# ACS_schematic.net
KiCad netlist of a schematic drawn in EAGLE
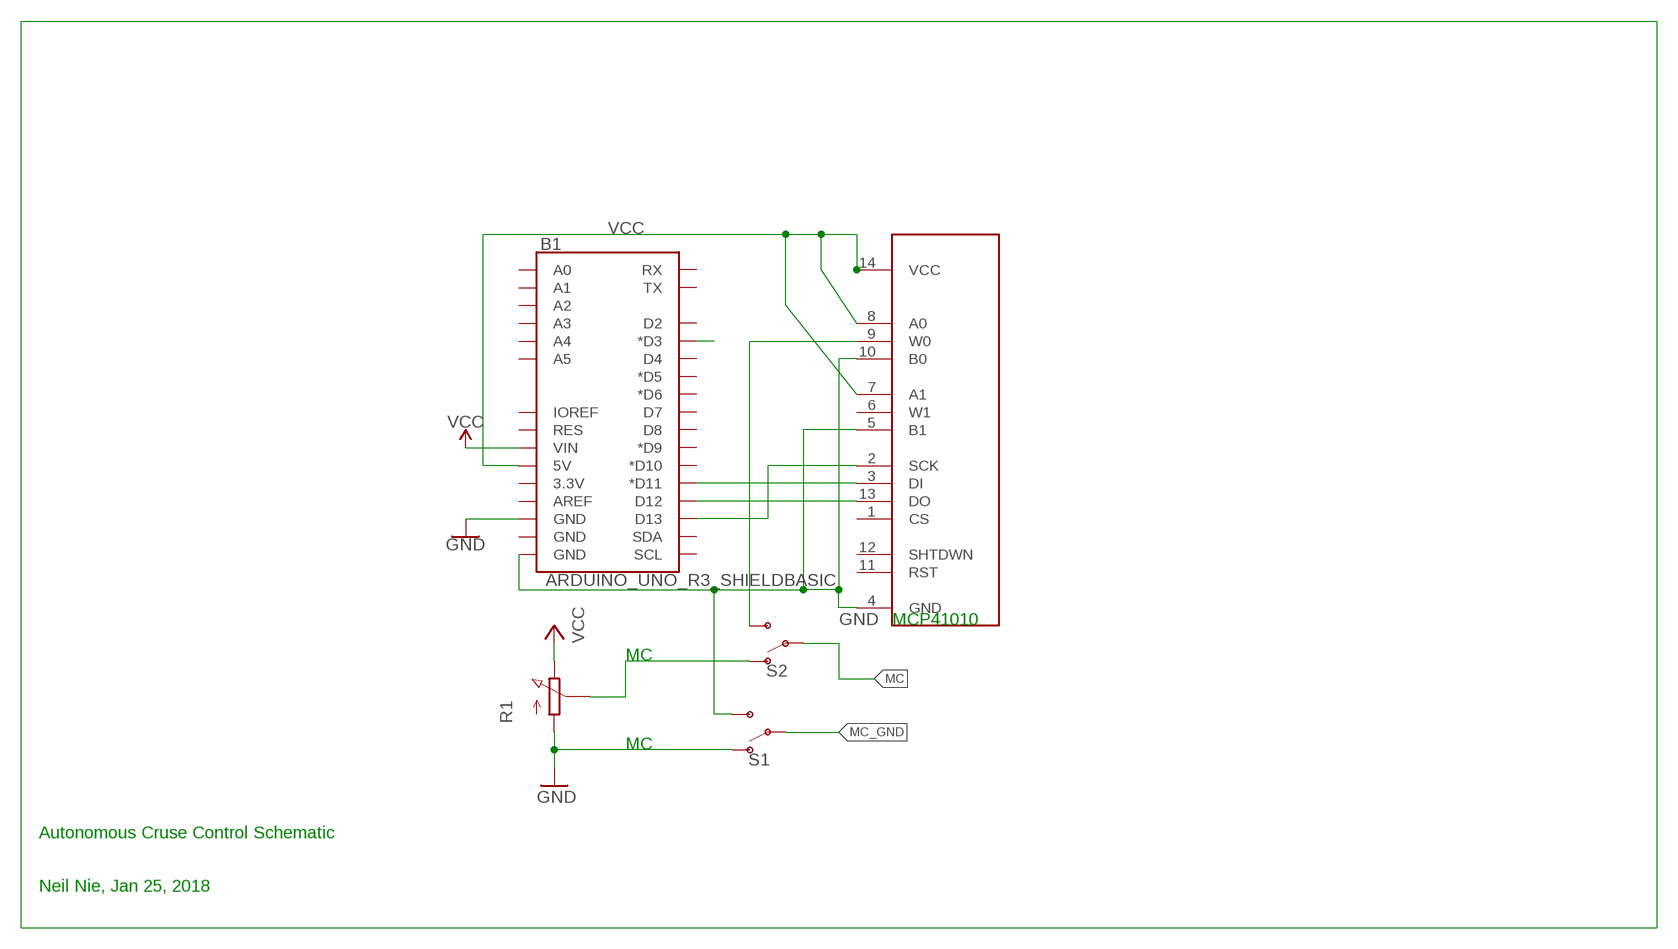
[diagram p0: schematic, sheet 1]

(export (version "E")
  (design (tool "Eeschema 10.0.6"))
  (components
    (comp (ref "B1")
      (value "ARDUINO_UNO_R3_SHIELDBASIC")
      (footprint "eagle-import:UNO_R3_SHIELD")
      (libsource (lib "eagle-import") (part "ARDUINO_UNO_R3_SHIELDBASIC"))
    )
    (comp (ref "MCP41010")
      (value "MCP42XXX")
      (footprint "eagle-import:SO014")
      (libsource (lib "eagle-import") (part "MCP42XXX"))
    )
    (comp (ref "R1")
      (value "PC25")
      (footprint "eagle-import:PC25")
      (fields (field (name "MF") "CLAROSTAT") (field (name "MPN") "308NPC25KS"))
      (libsource (lib "eagle-import") (part "PC25"))
    )
    (comp (ref "S1")
      (value "SWITCH-SPDT-PTH-11.6X4.0MM")
      (footprint "eagle-import:SWITCH_SPDT_PTH_11.6X4.0MM")
      (libsource (lib "eagle-import") (part "SWITCH-SPDT-PTH-11.6X4.0MM"))
    )
    (comp (ref "S2")
      (value "SWITCH-SPDT-PTH-11.6X4.0MM")
      (footprint "eagle-import:SWITCH_SPDT_PTH_11.6X4.0MM")
      (libsource (lib "eagle-import") (part "SWITCH-SPDT-PTH-11.6X4.0MM"))
    )
  )
  (nets
    (net (code "1") (name "GND") (class "Default")
      (node (ref "B1") (pin "GND@0") (pinfunction "GND_GND@0") (pintype "bidirectional"))
      (node (ref "B1") (pin "GND@2") (pinfunction "GND_GND@2") (pintype "bidirectional"))
      (node (ref "MCP41010") (pin "10") (pinfunction "B0_10") (pintype "bidirectional"))
      (node (ref "MCP41010") (pin "4") (pinfunction "GND_4") (pintype "bidirectional"))
      (node (ref "MCP41010") (pin "5") (pinfunction "B1_5") (pintype "bidirectional"))
      (node (ref "R1") (pin "A") (pinfunction "A_A") (pintype "passive"))
      (node (ref "S1") (pin "1") (pinfunction "O_1") (pintype "passive"))
      (node (ref "S1") (pin "3") (pinfunction "S_3") (pintype "passive"))
    )
    (net (code "2") (name "MC") (class "Default")
      (node (ref "S2") (pin "2") (pinfunction "P_2") (pintype "passive"))
    )
    (net (code "3") (name "MC_GND") (class "Default")
      (node (ref "S1") (pin "2") (pinfunction "P_2") (pintype "passive"))
    )
    (net (code "4") (name "Net-(B1-*D11)") (class "Default")
      (node (ref "B1") (pin "D11") (pinfunction "*D11_D11") (pintype "bidirectional"))
      (node (ref "MCP41010") (pin "3") (pinfunction "DI_3") (pintype "bidirectional"))
    )
    (net (code "5") (name "Net-(MCP41010-DO)") (class "Default")
      (node (ref "B1") (pin "D12") (pinfunction "D12_D12") (pintype "bidirectional"))
      (node (ref "MCP41010") (pin "13") (pinfunction "DO_13") (pintype "bidirectional"))
    )
    (net (code "6") (name "Net-(MCP41010-SCK)") (class "Default")
      (node (ref "B1") (pin "D13") (pinfunction "D13_D13") (pintype "bidirectional"))
      (node (ref "MCP41010") (pin "2") (pinfunction "SCK_2") (pintype "bidirectional"))
    )
    (net (code "7") (name "Net-(MCP41010-W0)") (class "Default")
      (node (ref "MCP41010") (pin "9") (pinfunction "W0_9") (pintype "bidirectional"))
      (node (ref "S2") (pin "3") (pinfunction "S_3") (pintype "passive"))
    )
    (net (code "8") (name "Net-(S2-O)") (class "Default")
      (node (ref "R1") (pin "S") (pinfunction "S_S") (pintype "passive"))
      (node (ref "S2") (pin "1") (pinfunction "O_1") (pintype "passive"))
    )
    (net (code "9") (name "VCC") (class "Default")
      (node (ref "B1") (pin "5V") (pinfunction "5V_5V") (pintype "bidirectional"))
      (node (ref "B1") (pin "VIN") (pinfunction "VIN_VIN") (pintype "bidirectional"))
      (node (ref "MCP41010") (pin "14") (pinfunction "VCC_14") (pintype "bidirectional"))
      (node (ref "MCP41010") (pin "7") (pinfunction "A1_7") (pintype "bidirectional"))
      (node (ref "MCP41010") (pin "8") (pinfunction "A0_8") (pintype "bidirectional"))
      (node (ref "R1") (pin "E") (pinfunction "E_E") (pintype "passive"))
    )
    (net (code "10") (name "unconnected-(B1-*D3-PadD3)") (class "Default")
      (node (ref "B1") (pin "D3") (pinfunction "*D3_D3") (pintype "bidirectional"))
    )
    (net (code "11") (name "unconnected-(B1-*D5-PadD5)") (class "Default")
      (node (ref "B1") (pin "D5") (pinfunction "*D5_D5") (pintype "bidirectional"))
    )
    (net (code "12") (name "unconnected-(B1-*D6-PadD6)") (class "Default")
      (node (ref "B1") (pin "D6") (pinfunction "*D6_D6") (pintype "bidirectional"))
    )
    (net (code "13") (name "unconnected-(B1-*D9-PadD9)") (class "Default")
      (node (ref "B1") (pin "D9") (pinfunction "*D9_D9") (pintype "bidirectional"))
    )
    (net (code "14") (name "unconnected-(B1-*D10-PadD10)") (class "Default")
      (node (ref "B1") (pin "D10") (pinfunction "*D10_D10") (pintype "bidirectional"))
    )
    (net (code "15") (name "unconnected-(B1-GND-PadGND@1)") (class "Default")
      (node (ref "B1") (pin "GND@1") (pinfunction "GND_GND@1") (pintype "bidirectional"))
    )
    (net (code "16") (name "unconnected-(B1-Pad3.3V)") (class "Default")
      (node (ref "B1") (pin "3.3V") (pinfunction "3.3V_3.3V") (pintype "bidirectional"))
    )
    (net (code "17") (name "unconnected-(B1-PadA0)") (class "Default")
      (node (ref "B1") (pin "A0") (pinfunction "A0_A0") (pintype "bidirectional"))
    )
    (net (code "18") (name "unconnected-(B1-PadA1)") (class "Default")
      (node (ref "B1") (pin "A1") (pinfunction "A1_A1") (pintype "bidirectional"))
    )
    (net (code "19") (name "unconnected-(B1-PadA2)") (class "Default")
      (node (ref "B1") (pin "A2") (pinfunction "A2_A2") (pintype "bidirectional"))
    )
    (net (code "20") (name "unconnected-(B1-PadA3)") (class "Default")
      (node (ref "B1") (pin "A3") (pinfunction "A3_A3") (pintype "bidirectional"))
    )
    (net (code "21") (name "unconnected-(B1-PadA4)") (class "Default")
      (node (ref "B1") (pin "A4") (pinfunction "A4_A4") (pintype "bidirectional"))
    )
    (net (code "22") (name "unconnected-(B1-PadA5)") (class "Default")
      (node (ref "B1") (pin "A5") (pinfunction "A5_A5") (pintype "bidirectional"))
    )
    (net (code "23") (name "unconnected-(B1-PadAREF)") (class "Default")
      (node (ref "B1") (pin "AREF") (pinfunction "AREF_AREF") (pintype "bidirectional"))
    )
    (net (code "24") (name "unconnected-(B1-PadD2)") (class "Default")
      (node (ref "B1") (pin "D2") (pinfunction "D2_D2") (pintype "bidirectional"))
    )
    (net (code "25") (name "unconnected-(B1-PadD4)") (class "Default")
      (node (ref "B1") (pin "D4") (pinfunction "D4_D4") (pintype "bidirectional"))
    )
    (net (code "26") (name "unconnected-(B1-PadD7)") (class "Default")
      (node (ref "B1") (pin "D7") (pinfunction "D7_D7") (pintype "bidirectional"))
    )
    (net (code "27") (name "unconnected-(B1-PadD8)") (class "Default")
      (node (ref "B1") (pin "D8") (pinfunction "D8_D8") (pintype "bidirectional"))
    )
    (net (code "28") (name "unconnected-(B1-PadIOREF)") (class "Default")
      (node (ref "B1") (pin "IOREF") (pinfunction "IOREF_IOREF") (pintype "bidirectional"))
    )
    (net (code "29") (name "unconnected-(B1-PadRES)") (class "Default")
      (node (ref "B1") (pin "RES") (pinfunction "RES_RES") (pintype "bidirectional"))
    )
    (net (code "30") (name "unconnected-(B1-PadRX)") (class "Default")
      (node (ref "B1") (pin "RX") (pinfunction "RX_RX") (pintype "bidirectional"))
    )
    (net (code "31") (name "unconnected-(B1-PadSCL)") (class "Default")
      (node (ref "B1") (pin "SCL") (pinfunction "SCL_SCL") (pintype "bidirectional"))
    )
    (net (code "32") (name "unconnected-(B1-PadSDA)") (class "Default")
      (node (ref "B1") (pin "SDA") (pinfunction "SDA_SDA") (pintype "bidirectional"))
    )
    (net (code "33") (name "unconnected-(B1-PadTX)") (class "Default")
      (node (ref "B1") (pin "TX") (pinfunction "TX_TX") (pintype "bidirectional"))
    )
    (net (code "34") (name "unconnected-(MCP41010-CS-Pad1)") (class "Default")
      (node (ref "MCP41010") (pin "1") (pinfunction "CS_1") (pintype "bidirectional"))
    )
    (net (code "35") (name "unconnected-(MCP41010-RST-Pad11)") (class "Default")
      (node (ref "MCP41010") (pin "11") (pinfunction "RST_11") (pintype "bidirectional"))
    )
    (net (code "36") (name "unconnected-(MCP41010-SHTDWN-Pad12)") (class "Default")
      (node (ref "MCP41010") (pin "12") (pinfunction "SHTDWN_12") (pintype "bidirectional"))
    )
    (net (code "37") (name "unconnected-(MCP41010-W1-Pad6)") (class "Default")
      (node (ref "MCP41010") (pin "6") (pinfunction "W1_6") (pintype "bidirectional"))
    )
  )
)
